# M128_EX.net
KiCad netlist of a schematic drawn in Altium Designer
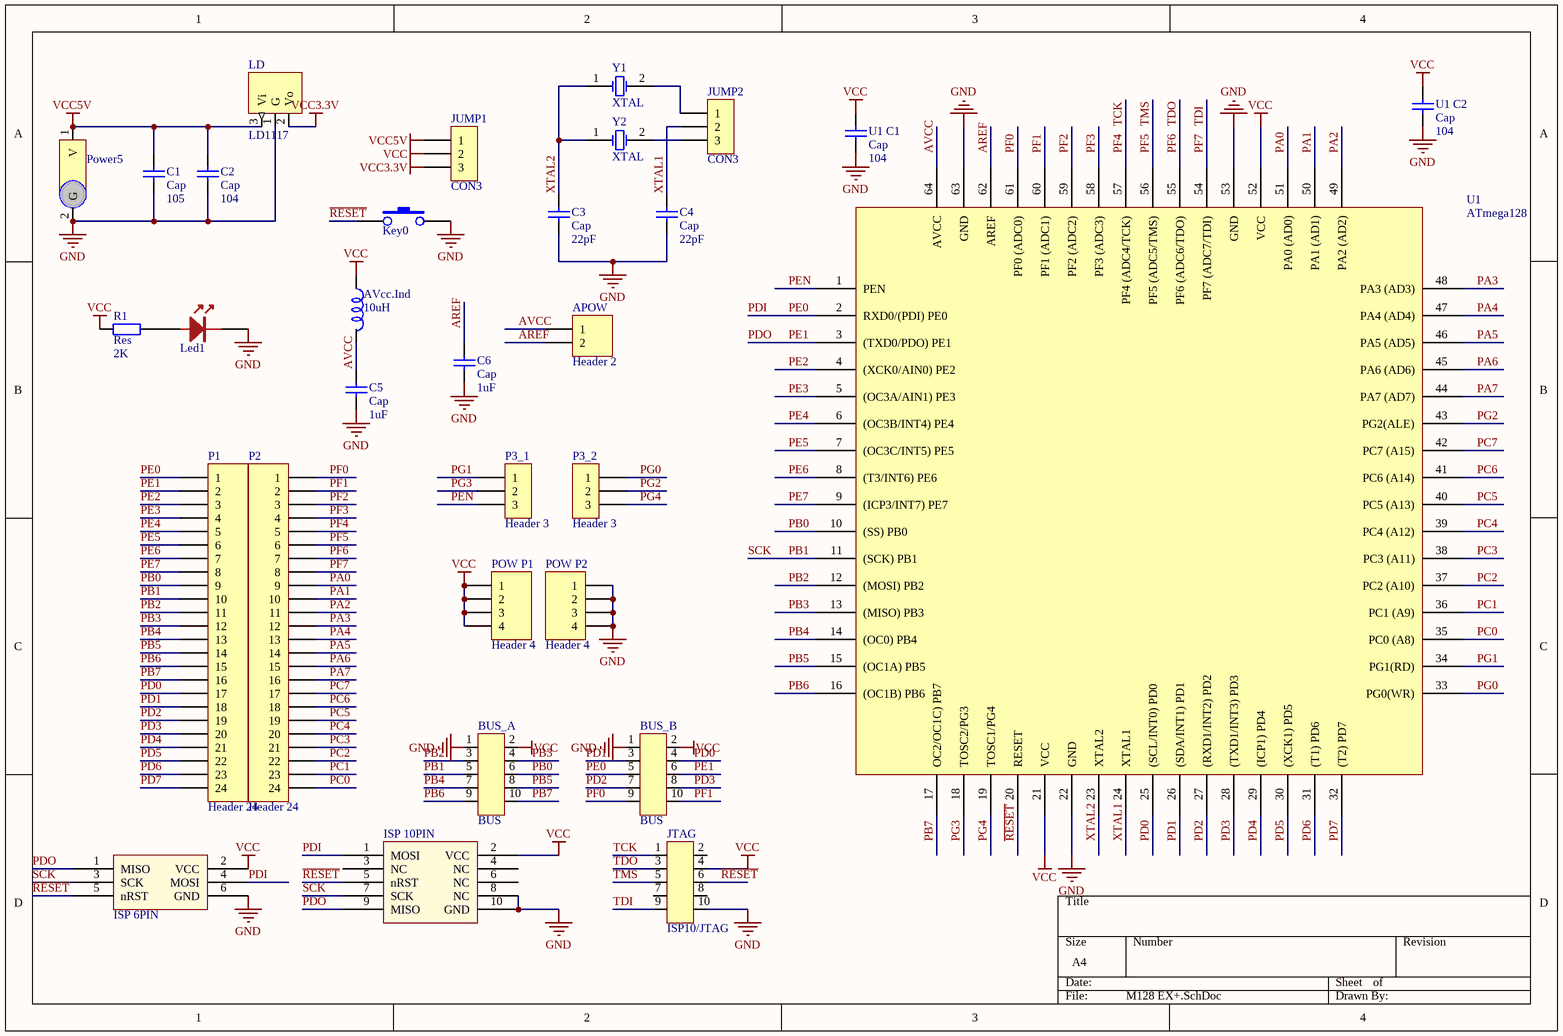
[diagram p0: M128 EX+.SchDoc]

(export (version "E")
  (design (tool "Eeschema 10.0.6"))
  (components
    (comp (ref "APOW")
      (value "Header 2")
      (footprint "SIP2")
      (description "Header, 2-Pin")
      (fields (field (name "PUBLISHER") "Altium Limited"))
      (libsource (lib "zz") (part "Header 2"))
    )
    (comp (ref "AVcc.Ind") (value "10uH") (footprint "RES") (libsource (lib "zz") (part "IND")))
    (comp (ref "BUS_A")
      (value "BUS")
      (footprint "ISP_10")
      (description "ISP_10")
      (libsource (lib "zz") (part "ISP_10"))
    )
    (comp (ref "BUS_B")
      (value "BUS")
      (footprint "ISP_10")
      (description "ISP_10")
      (libsource (lib "zz") (part "ISP_10"))
    )
    (comp (ref "C1")
      (value "Cap")
      (footprint "0805")
      (description "Capacitor")
      (fields (field (name "ALTIUM_VALUE") "105") (field (name "PUBLISHER") "Altium Limited"))
      (libsource (lib "Miscellaneous Devices") (part "Cap"))
    )
    (comp (ref "C2")
      (value "Cap")
      (footprint "0805")
      (description "Capacitor")
      (fields (field (name "ALTIUM_VALUE") "104") (field (name "PUBLISHER") "Altium Limited"))
      (libsource (lib "Miscellaneous Devices") (part "Cap"))
    )
    (comp (ref "C3")
      (value "Cap")
      (footprint "0603")
      (description "Capacitor")
      (fields (field (name "ALTIUM_VALUE") "22pF") (field (name "PUBLISHER") "Altium Limited"))
      (libsource (lib "Miscellaneous Devices") (part "Cap"))
    )
    (comp (ref "C4")
      (value "Cap")
      (footprint "0603")
      (description "Capacitor")
      (fields (field (name "ALTIUM_VALUE") "22pF") (field (name "PUBLISHER") "Altium Limited"))
      (libsource (lib "Miscellaneous Devices") (part "Cap"))
    )
    (comp (ref "C5")
      (value "Cap")
      (footprint "0805")
      (description "Capacitor")
      (fields (field (name "ALTIUM_VALUE") "1uF") (field (name "PUBLISHER") "Altium Limited"))
      (libsource (lib "Miscellaneous Devices") (part "Cap"))
    )
    (comp (ref "C6")
      (value "Cap")
      (footprint "0805")
      (description "Capacitor")
      (fields (field (name "ALTIUM_VALUE") "1uF") (field (name "PUBLISHER") "Altium Limited"))
      (libsource (lib "Miscellaneous Devices") (part "Cap"))
    )
    (comp (ref "ISP 6PIN") (value "ISP 6PIN") (footprint "ISP_6") (libsource (lib "zz") (part "ISP 6PIN")))
    (comp (ref "ISP 10PIN")
      (value "ISP 10PIN")
      (footprint "ISP_10")
      (libsource (lib "zz") (part "ISP 10PIN"))
    )
    (comp (ref "JTAG")
      (value "ISP10/JTAG")
      (footprint "ISP_10")
      (description "ISP_10")
      (libsource (lib "zz") (part "ISP_10"))
    )
    (comp (ref "JUMP1")
      (value "CON3")
      (footprint "SIP3")
      (description "Connector")
      (libsource (lib "zz") (part "CON3"))
    )
    (comp (ref "JUMP2")
      (value "CON3")
      (footprint "SIP3")
      (description "Connector")
      (libsource (lib "zz") (part "CON3"))
    )
    (comp (ref "Key0") (value "PB2") (footprint "KEY") (libsource (lib "zz") (part "KEY")))
    (comp (ref "LD") (value "LD1117") (footprint "LD1117-3.3") (libsource (lib "zz") (part "LD1117")))
    (comp (ref "Led1") (value "Led1") (footprint "0805_LED") (libsource (lib "zz") (part "LED")))
    (comp (ref "P1")
      (value "Header 24")
      (footprint "SIP24")
      (description "Header, 24-Pin")
      (fields (field (name "PUBLISHER") "Altium Limited"))
      (libsource (lib "zz") (part "Header 24"))
    )
    (comp (ref "P2")
      (value "Header 24")
      (footprint "SIP24")
      (description "Header, 24-Pin")
      (fields (field (name "PUBLISHER") "Altium Limited"))
      (libsource (lib "") (part "Header 24_1"))
    )
    (comp (ref "P3_1")
      (value "Header 3")
      (footprint "SIP3")
      (description "Header, 3-Pin")
      (libsource (lib "") (part "Header 3_1"))
    )
    (comp (ref "P3_2")
      (value "Header 3")
      (footprint "SIP3")
      (description "Header, 3-Pin")
      (libsource (lib "zz") (part "Header 3"))
    )
    (comp (ref "POW P1")
      (value "Header 4")
      (footprint "SIP4")
      (description "Header, 4-Pin")
      (fields (field (name "PUBLISHER") "Altium Limited"))
      (libsource (lib "zz") (part "Header 4"))
    )
    (comp (ref "POW P2")
      (value "Header 4")
      (footprint "SIP4")
      (description "Header, 4-Pin")
      (fields (field (name "PUBLISHER") "Altium Limited"))
      (libsource (lib "") (part "Header 4_1"))
    )
    (comp (ref "Power5")
      (value "5V")
      (footprint "PWR_5V")
      (description "Power5")
      (libsource (lib "zz") (part "Power5"))
    )
    (comp (ref "R1")
      (value "Res")
      (footprint "0603")
      (description "Resistor")
      (fields (field (name "ALTIUM_VALUE") "2K") (field (name "PUBLISHER") "Altium Limited"))
      (libsource (lib "Miscellaneous Devices") (part "Res2"))
    )
    (comp (ref "U1") (value "ATmega128") (footprint "TQFP64") (libsource (lib "zz") (part "ATmega128")))
    (comp (ref "U1 C1")
      (value "Cap")
      (footprint "0805")
      (description "Capacitor")
      (fields (field (name "ALTIUM_VALUE") "104") (field (name "PUBLISHER") "Altium Limited"))
      (libsource (lib "Miscellaneous Devices") (part "Cap"))
    )
    (comp (ref "U1 C2")
      (value "Cap")
      (footprint "0805")
      (description "Capacitor")
      (fields (field (name "ALTIUM_VALUE") "104") (field (name "PUBLISHER") "Altium Limited"))
      (libsource (lib "Miscellaneous Devices") (part "Cap"))
    )
    (comp (ref "Y1")
      (value "XTAL")
      (footprint "CRYSTAL")
      (description "Crystal Oscillator")
      (fields (field (name "PUBLISHER") "Altium Limited"))
      (libsource (lib "zz") (part "XTAL"))
    )
    (comp (ref "Y2")
      (value "XTAL")
      (footprint "CRYSTAL2")
      (description "Crystal Oscillator")
      (fields (field (name "PUBLISHER") "Altium Limited"))
      (libsource (lib "zz") (part "XTAL"))
    )
  )
  (nets
    (net (code "1") (name "/AREF") (class "Default")
      (node (ref "APOW") (pin "2") (pinfunction "2_2") (pintype "passive"))
      (node (ref "C6") (pin "2") (pinfunction "2_2") (pintype "passive"))
      (node (ref "U1") (pin "62") (pinfunction "AREF_62") (pintype "passive"))
    )
    (net (code "2") (name "/AVCC") (class "Default")
      (node (ref "APOW") (pin "1") (pinfunction "1_1") (pintype "passive"))
      (node (ref "AVcc.Ind") (pin "2") (pinfunction "1_2") (pintype "passive"))
      (node (ref "C5") (pin "2") (pinfunction "2_2") (pintype "passive"))
      (node (ref "U1") (pin "64") (pinfunction "AVCC_64") (pintype "passive"))
    )
    (net (code "3") (name "/PA0") (class "Default")
      (node (ref "P2") (pin "9") (pinfunction "9_9") (pintype "passive"))
      (node (ref "U1") (pin "51") (pinfunction "PA0_(AD0)_51") (pintype "passive"))
    )
    (net (code "4") (name "/PA1") (class "Default")
      (node (ref "P2") (pin "10") (pinfunction "10_10") (pintype "passive"))
      (node (ref "U1") (pin "50") (pinfunction "PA1_(AD1)_50") (pintype "passive"))
    )
    (net (code "5") (name "/PA2") (class "Default")
      (node (ref "P2") (pin "11") (pinfunction "11_11") (pintype "passive"))
      (node (ref "U1") (pin "49") (pinfunction "PA2_(AD2)_49") (pintype "passive"))
    )
    (net (code "6") (name "/PA3") (class "Default")
      (node (ref "P2") (pin "12") (pinfunction "12_12") (pintype "passive"))
      (node (ref "U1") (pin "48") (pinfunction "PA3_(AD3)_48") (pintype "passive"))
    )
    (net (code "7") (name "/PA4") (class "Default")
      (node (ref "P2") (pin "13") (pinfunction "13_13") (pintype "passive"))
      (node (ref "U1") (pin "47") (pinfunction "PA4_(AD4)_47") (pintype "passive"))
    )
    (net (code "8") (name "/PA5") (class "Default")
      (node (ref "P2") (pin "14") (pinfunction "14_14") (pintype "passive"))
      (node (ref "U1") (pin "46") (pinfunction "PA5_(AD5)_46") (pintype "passive"))
    )
    (net (code "9") (name "/PA6") (class "Default")
      (node (ref "P2") (pin "15") (pinfunction "15_15") (pintype "passive"))
      (node (ref "U1") (pin "45") (pinfunction "PA6_(AD6)_45") (pintype "passive"))
    )
    (net (code "10") (name "/PA7") (class "Default")
      (node (ref "P2") (pin "16") (pinfunction "16_16") (pintype "passive"))
      (node (ref "U1") (pin "44") (pinfunction "PA7_(AD7)_44") (pintype "passive"))
    )
    (net (code "11") (name "/PB0") (class "Default")
      (node (ref "BUS_A") (pin "6") (pintype "passive"))
      (node (ref "P1") (pin "9") (pinfunction "9_9") (pintype "passive"))
      (node (ref "U1") (pin "10") (pinfunction "(SS)_PB0_10") (pintype "passive"))
    )
    (net (code "12") (name "/PB1") (class "Default")
      (node (ref "BUS_A") (pin "5") (pintype "passive"))
      (node (ref "ISP 10PIN") (pin "7") (pinfunction "SCK_7") (pintype "passive"))
      (node (ref "ISP 6PIN") (pin "3") (pinfunction "SCK_3") (pintype "passive"))
      (node (ref "P1") (pin "10") (pinfunction "10_10") (pintype "passive"))
      (node (ref "U1") (pin "11") (pinfunction "(SCK)_PB1_11") (pintype "passive"))
    )
    (net (code "13") (name "/PB2") (class "Default")
      (node (ref "BUS_A") (pin "3") (pintype "passive"))
      (node (ref "P1") (pin "11") (pinfunction "11_11") (pintype "passive"))
      (node (ref "U1") (pin "12") (pinfunction "(MOSI)_PB2_12") (pintype "passive"))
    )
    (net (code "14") (name "/PB3") (class "Default")
      (node (ref "BUS_A") (pin "4") (pintype "passive"))
      (node (ref "P1") (pin "12") (pinfunction "12_12") (pintype "passive"))
      (node (ref "U1") (pin "13") (pinfunction "(MISO)_PB3_13") (pintype "passive"))
    )
    (net (code "15") (name "/PB4") (class "Default")
      (node (ref "BUS_A") (pin "7") (pintype "passive"))
      (node (ref "P1") (pin "13") (pinfunction "13_13") (pintype "passive"))
      (node (ref "U1") (pin "14") (pinfunction "(OC0)_PB4_14") (pintype "passive"))
    )
    (net (code "16") (name "/PB5") (class "Default")
      (node (ref "BUS_A") (pin "8") (pintype "passive"))
      (node (ref "P1") (pin "14") (pinfunction "14_14") (pintype "passive"))
      (node (ref "U1") (pin "15") (pinfunction "(OC1A)_PB5_15") (pintype "passive"))
    )
    (net (code "17") (name "/PB6") (class "Default")
      (node (ref "BUS_A") (pin "9") (pintype "passive"))
      (node (ref "P1") (pin "15") (pinfunction "15_15") (pintype "passive"))
      (node (ref "U1") (pin "16") (pinfunction "(OC1B)_PB6_16") (pintype "passive"))
    )
    (net (code "18") (name "/PB7") (class "Default")
      (node (ref "BUS_A") (pin "10") (pintype "passive"))
      (node (ref "P1") (pin "16") (pinfunction "16_16") (pintype "passive"))
      (node (ref "U1") (pin "17") (pinfunction "OC2/OC1C)_PB7_17") (pintype "passive"))
    )
    (net (code "19") (name "/PC0") (class "Default")
      (node (ref "P2") (pin "24") (pinfunction "24_24") (pintype "passive"))
      (node (ref "U1") (pin "35") (pinfunction "PC0_(A8)_35") (pintype "passive"))
    )
    (net (code "20") (name "/PC1") (class "Default")
      (node (ref "P2") (pin "23") (pinfunction "23_23") (pintype "passive"))
      (node (ref "U1") (pin "36") (pinfunction "PC1_(A9)_36") (pintype "passive"))
    )
    (net (code "21") (name "/PC2") (class "Default")
      (node (ref "P2") (pin "22") (pinfunction "22_22") (pintype "passive"))
      (node (ref "U1") (pin "37") (pinfunction "PC2_(A10)_37") (pintype "passive"))
    )
    (net (code "22") (name "/PC3") (class "Default")
      (node (ref "P2") (pin "21") (pinfunction "21_21") (pintype "passive"))
      (node (ref "U1") (pin "38") (pinfunction "PC3_(A11)_38") (pintype "passive"))
    )
    (net (code "23") (name "/PC4") (class "Default")
      (node (ref "P2") (pin "20") (pinfunction "20_20") (pintype "passive"))
      (node (ref "U1") (pin "39") (pinfunction "PC4_(A12)_39") (pintype "passive"))
    )
    (net (code "24") (name "/PC5") (class "Default")
      (node (ref "P2") (pin "19") (pinfunction "19_19") (pintype "passive"))
      (node (ref "U1") (pin "40") (pinfunction "PC5_(A13)_40") (pintype "passive"))
    )
    (net (code "25") (name "/PC6") (class "Default")
      (node (ref "P2") (pin "18") (pinfunction "18_18") (pintype "passive"))
      (node (ref "U1") (pin "41") (pinfunction "PC6_(A14)_41") (pintype "passive"))
    )
    (net (code "26") (name "/PC7") (class "Default")
      (node (ref "P2") (pin "17") (pinfunction "17_17") (pintype "passive"))
      (node (ref "U1") (pin "42") (pinfunction "PC7_(A15)_42") (pintype "passive"))
    )
    (net (code "27") (name "/PD0") (class "Default")
      (node (ref "BUS_B") (pin "4") (pintype "passive"))
      (node (ref "P1") (pin "17") (pinfunction "17_17") (pintype "passive"))
      (node (ref "U1") (pin "25") (pinfunction "(SCL/INT0)_PD0_25") (pintype "passive"))
    )
    (net (code "28") (name "/PD1") (class "Default")
      (node (ref "BUS_B") (pin "3") (pintype "passive"))
      (node (ref "P1") (pin "18") (pinfunction "18_18") (pintype "passive"))
      (node (ref "U1") (pin "26") (pinfunction "(SDA/INT1)_PD1_26") (pintype "passive"))
    )
    (net (code "29") (name "/PD2") (class "Default")
      (node (ref "BUS_B") (pin "7") (pintype "passive"))
      (node (ref "P1") (pin "19") (pinfunction "19_19") (pintype "passive"))
      (node (ref "U1") (pin "27") (pinfunction "(RXD1/INT2)_PD2_27") (pintype "passive"))
    )
    (net (code "30") (name "/PD3") (class "Default")
      (node (ref "BUS_B") (pin "8") (pintype "passive"))
      (node (ref "P1") (pin "20") (pinfunction "20_20") (pintype "passive"))
      (node (ref "U1") (pin "28") (pinfunction "(TXD1/INT3)_PD3_28") (pintype "passive"))
    )
    (net (code "31") (name "/PD4") (class "Default")
      (node (ref "P1") (pin "21") (pinfunction "21_21") (pintype "passive"))
      (node (ref "U1") (pin "29") (pinfunction "(ICP1)_PD4_29") (pintype "passive"))
    )
    (net (code "32") (name "/PD5") (class "Default")
      (node (ref "P1") (pin "22") (pinfunction "22_22") (pintype "passive"))
      (node (ref "U1") (pin "30") (pinfunction "(XCK1)_PD5_30") (pintype "passive"))
    )
    (net (code "33") (name "/PD6") (class "Default")
      (node (ref "P1") (pin "23") (pinfunction "23_23") (pintype "passive"))
      (node (ref "U1") (pin "31") (pinfunction "(T1)_PD6_31") (pintype "passive"))
    )
    (net (code "34") (name "/PD7") (class "Default")
      (node (ref "P1") (pin "24") (pinfunction "24_24") (pintype "passive"))
      (node (ref "U1") (pin "32") (pinfunction "(T2)_PD7_32") (pintype "passive"))
    )
    (net (code "35") (name "/PDI") (class "Default")
      (node (ref "BUS_B") (pin "5") (pintype "passive"))
      (node (ref "ISP 10PIN") (pin "1") (pinfunction "MOSI_1") (pintype "passive"))
      (node (ref "ISP 6PIN") (pin "4") (pinfunction "MOSI_4") (pintype "passive"))
      (node (ref "P1") (pin "1") (pinfunction "1_1") (pintype "passive"))
      (node (ref "U1") (pin "2") (pinfunction "RXD0/(PDI)_PE0_2") (pintype "passive"))
    )
    (net (code "36") (name "/PDO") (class "Default")
      (node (ref "BUS_B") (pin "6") (pintype "passive"))
      (node (ref "ISP 10PIN") (pin "9") (pinfunction "MISO_9") (pintype "passive"))
      (node (ref "ISP 6PIN") (pin "1") (pinfunction "MISO_1") (pintype "passive"))
      (node (ref "P1") (pin "2") (pinfunction "2_2") (pintype "passive"))
      (node (ref "U1") (pin "3") (pinfunction "(TXD0/PDO)_PE1_3") (pintype "passive"))
    )
    (net (code "37") (name "/PE2") (class "Default")
      (node (ref "P1") (pin "3") (pinfunction "3_3") (pintype "passive"))
      (node (ref "U1") (pin "4") (pinfunction "(XCK0/AIN0)_PE2_4") (pintype "passive"))
    )
    (net (code "38") (name "/PE3") (class "Default")
      (node (ref "P1") (pin "4") (pinfunction "4_4") (pintype "passive"))
      (node (ref "U1") (pin "5") (pinfunction "(OC3A/AIN1)_PE3_5") (pintype "passive"))
    )
    (net (code "39") (name "/PE4") (class "Default")
      (node (ref "P1") (pin "5") (pinfunction "5_5") (pintype "passive"))
      (node (ref "U1") (pin "6") (pinfunction "(OC3B/INT4)_PE4_6") (pintype "passive"))
    )
    (net (code "40") (name "/PE5") (class "Default")
      (node (ref "P1") (pin "6") (pinfunction "6_6") (pintype "passive"))
      (node (ref "U1") (pin "7") (pinfunction "(OC3C/INT5)_PE5_7") (pintype "passive"))
    )
    (net (code "41") (name "/PE6") (class "Default")
      (node (ref "P1") (pin "7") (pinfunction "7_7") (pintype "passive"))
      (node (ref "U1") (pin "8") (pinfunction "(T3/INT6)_PE6_8") (pintype "passive"))
    )
    (net (code "42") (name "/PE7") (class "Default")
      (node (ref "P1") (pin "8") (pinfunction "8_8") (pintype "passive"))
      (node (ref "U1") (pin "9") (pinfunction "(ICP3/INT7)_PE7_9") (pintype "passive"))
    )
    (net (code "43") (name "/PEN") (class "Default")
      (node (ref "P3_1") (pin "3") (pinfunction "3_3") (pintype "passive"))
      (node (ref "U1") (pin "1") (pinfunction "PEN_1") (pintype "passive"))
    )
    (net (code "44") (name "/PF0") (class "Default")
      (node (ref "BUS_B") (pin "9") (pintype "passive"))
      (node (ref "P2") (pin "1") (pinfunction "1_1") (pintype "passive"))
      (node (ref "U1") (pin "61") (pinfunction "PF0_(ADC0)_61") (pintype "passive"))
    )
    (net (code "45") (name "/PF1") (class "Default")
      (node (ref "BUS_B") (pin "10") (pintype "passive"))
      (node (ref "P2") (pin "2") (pinfunction "2_2") (pintype "passive"))
      (node (ref "U1") (pin "60") (pinfunction "PF1_(ADC1)_60") (pintype "passive"))
    )
    (net (code "46") (name "/PF2") (class "Default")
      (node (ref "P2") (pin "3") (pinfunction "3_3") (pintype "passive"))
      (node (ref "U1") (pin "59") (pinfunction "PF2_(ADC2)_59") (pintype "passive"))
    )
    (net (code "47") (name "/PF3") (class "Default")
      (node (ref "P2") (pin "4") (pinfunction "4_4") (pintype "passive"))
      (node (ref "U1") (pin "58") (pinfunction "PF3_(ADC3)_58") (pintype "passive"))
    )
    (net (code "48") (name "/PF4") (class "Default")
      (node (ref "JTAG") (pin "1") (pintype "passive"))
      (node (ref "P2") (pin "5") (pinfunction "5_5") (pintype "passive"))
      (node (ref "U1") (pin "57") (pinfunction "PF4_(ADC4/TCK)_57") (pintype "passive"))
    )
    (net (code "49") (name "/PF5") (class "Default")
      (node (ref "JTAG") (pin "5") (pintype "passive"))
      (node (ref "P2") (pin "6") (pinfunction "6_6") (pintype "passive"))
      (node (ref "U1") (pin "56") (pinfunction "PF5_(ADC5/TMS)_56") (pintype "passive"))
    )
    (net (code "50") (name "/PF6") (class "Default")
      (node (ref "JTAG") (pin "3") (pintype "passive"))
      (node (ref "P2") (pin "7") (pinfunction "7_7") (pintype "passive"))
      (node (ref "U1") (pin "55") (pinfunction "PF6_(ADC6/TDO)_55") (pintype "passive"))
    )
    (net (code "51") (name "/PF7") (class "Default")
      (node (ref "JTAG") (pin "9") (pintype "passive"))
      (node (ref "P2") (pin "8") (pinfunction "8_8") (pintype "passive"))
      (node (ref "U1") (pin "54") (pinfunction "PF7_(ADC7/TDI)_54") (pintype "passive"))
    )
    (net (code "52") (name "/PG0") (class "Default")
      (node (ref "P3_2") (pin "1") (pinfunction "1_1") (pintype "passive"))
      (node (ref "U1") (pin "33") (pinfunction "PG0(WR)_33") (pintype "passive"))
    )
    (net (code "53") (name "/PG1") (class "Default")
      (node (ref "P3_1") (pin "1") (pinfunction "1_1") (pintype "passive"))
      (node (ref "U1") (pin "34") (pinfunction "PG1(RD)_34") (pintype "passive"))
    )
    (net (code "54") (name "/PG2") (class "Default")
      (node (ref "P3_2") (pin "2") (pinfunction "2_2") (pintype "passive"))
      (node (ref "U1") (pin "43") (pinfunction "PG2(ALE)_43") (pintype "passive"))
    )
    (net (code "55") (name "/PG3") (class "Default")
      (node (ref "P3_1") (pin "2") (pinfunction "2_2") (pintype "passive"))
      (node (ref "U1") (pin "18") (pinfunction "TOSC2/PG3_18") (pintype "passive"))
    )
    (net (code "56") (name "/PG4") (class "Default")
      (node (ref "P3_2") (pin "3") (pinfunction "3_3") (pintype "passive"))
      (node (ref "U1") (pin "19") (pinfunction "TOSC1/PG4_19") (pintype "passive"))
    )
    (net (code "57") (name "/XTAL1") (class "Default")
      (node (ref "C4") (pin "2") (pinfunction "2_2") (pintype "passive"))
      (node (ref "JUMP2") (pin "2") (pinfunction "2_2") (pintype "passive"))
      (node (ref "U1") (pin "24") (pinfunction "XTAL1_24") (pintype "passive"))
    )
    (net (code "58") (name "/XTAL2") (class "Default")
      (node (ref "C3") (pin "2") (pinfunction "2_2") (pintype "passive"))
      (node (ref "U1") (pin "23") (pinfunction "XTAL2_23") (pintype "passive"))
      (node (ref "Y1") (pin "1") (pinfunction "OSC1_1") (pintype "passive"))
      (node (ref "Y2") (pin "1") (pinfunction "OSC1_1") (pintype "passive"))
    )
    (net (code "59") (name "/~{RESET}") (class "Default")
      (node (ref "ISP 10PIN") (pin "5") (pinfunction "nRST_5") (pintype "passive"))
      (node (ref "ISP 6PIN") (pin "5") (pinfunction "nRST_5") (pintype "passive"))
      (node (ref "JTAG") (pin "6") (pintype "passive"))
      (node (ref "Key0") (pin "1") (pinfunction "1_1") (pintype "passive"))
      (node (ref "U1") (pin "20") (pinfunction "RESET_20") (pintype "passive"))
    )
    (net (code "60") (name "GND") (class "Default")
      (node (ref "BUS_A") (pin "1") (pintype "passive"))
      (node (ref "BUS_B") (pin "1") (pintype "passive"))
      (node (ref "C1") (pin "1") (pinfunction "1_1") (pintype "passive"))
      (node (ref "C2") (pin "1") (pinfunction "1_1") (pintype "passive"))
      (node (ref "C3") (pin "1") (pinfunction "1_1") (pintype "passive"))
      (node (ref "C4") (pin "1") (pinfunction "1_1") (pintype "passive"))
      (node (ref "C5") (pin "1") (pinfunction "1_1") (pintype "passive"))
      (node (ref "C6") (pin "1") (pinfunction "1_1") (pintype "passive"))
      (node (ref "ISP 10PIN") (pin "10") (pinfunction "GND_10") (pintype "passive"))
      (node (ref "ISP 10PIN") (pin "8") (pinfunction "NC_8") (pintype "passive"))
      (node (ref "ISP 6PIN") (pin "6") (pinfunction "GND_6") (pintype "passive"))
      (node (ref "JTAG") (pin "10") (pintype "passive"))
      (node (ref "Key0") (pin "2") (pinfunction "2_2") (pintype "passive"))
      (node (ref "LD") (pin "1") (pinfunction "G_1") (pintype "passive"))
      (node (ref "Led1") (pin "2") (pinfunction "2_2") (pintype "passive"))
      (node (ref "POW P2") (pin "1") (pinfunction "1_1") (pintype "passive"))
      (node (ref "POW P2") (pin "2") (pinfunction "2_2") (pintype "passive"))
      (node (ref "POW P2") (pin "3") (pinfunction "3_3") (pintype "passive"))
      (node (ref "POW P2") (pin "4") (pinfunction "4_4") (pintype "passive"))
      (node (ref "Power5") (pin "2") (pinfunction "G_2") (pintype "passive"))
      (node (ref "U1") (pin "22") (pinfunction "GND_22") (pintype "passive"))
      (node (ref "U1") (pin "53") (pinfunction "GND_53") (pintype "passive"))
      (node (ref "U1") (pin "63") (pinfunction "GND_63") (pintype "passive"))
      (node (ref "U1 C1") (pin "1") (pinfunction "1_1") (pintype "passive"))
      (node (ref "U1 C2") (pin "1") (pinfunction "1_1") (pintype "passive"))
    )
    (net (code "61") (name "Net-(Led1-Pad1)") (class "Default")
      (node (ref "Led1") (pin "1") (pinfunction "1_1") (pintype "passive"))
      (node (ref "R1") (pin "1") (pinfunction "1_1") (pintype "passive"))
    )
    (net (code "62") (name "Net-(Y1-OSC2)") (class "Default")
      (node (ref "JUMP2") (pin "1") (pinfunction "1_1") (pintype "passive"))
      (node (ref "Y1") (pin "2") (pinfunction "OSC2_2") (pintype "passive"))
    )
    (net (code "63") (name "Net-(Y2-OSC2)") (class "Default")
      (node (ref "JUMP2") (pin "3") (pinfunction "3_3") (pintype "passive"))
      (node (ref "Y2") (pin "2") (pinfunction "OSC2_2") (pintype "passive"))
    )
    (net (code "64") (name "VCC") (class "Default")
      (node (ref "AVcc.Ind") (pin "1") (pinfunction "0_1") (pintype "passive"))
      (node (ref "BUS_A") (pin "2") (pintype "passive"))
      (node (ref "BUS_B") (pin "2") (pintype "passive"))
      (node (ref "ISP 10PIN") (pin "2") (pinfunction "VCC_2") (pintype "passive"))
      (node (ref "ISP 6PIN") (pin "2") (pinfunction "VCC_2") (pintype "passive"))
      (node (ref "JTAG") (pin "4") (pintype "passive"))
      (node (ref "JUMP1") (pin "2") (pinfunction "2_2") (pintype "passive"))
      (node (ref "POW P1") (pin "1") (pinfunction "1_1") (pintype "passive"))
      (node (ref "POW P1") (pin "2") (pinfunction "2_2") (pintype "passive"))
      (node (ref "POW P1") (pin "3") (pinfunction "3_3") (pintype "passive"))
      (node (ref "POW P1") (pin "4") (pinfunction "4_4") (pintype "passive"))
      (node (ref "R1") (pin "2") (pinfunction "2_2") (pintype "passive"))
      (node (ref "U1") (pin "21") (pinfunction "VCC_21") (pintype "passive"))
      (node (ref "U1") (pin "52") (pinfunction "VCC_52") (pintype "passive"))
      (node (ref "U1 C1") (pin "2") (pinfunction "2_2") (pintype "passive"))
      (node (ref "U1 C2") (pin "2") (pinfunction "2_2") (pintype "passive"))
    )
    (net (code "65") (name "VCC3.3V") (class "Default")
      (node (ref "JUMP1") (pin "3") (pinfunction "3_3") (pintype "passive"))
      (node (ref "LD") (pin "2") (pinfunction "Vo_2") (pintype "passive"))
    )
    (net (code "66") (name "VCC5V") (class "Default")
      (node (ref "C1") (pin "2") (pinfunction "2_2") (pintype "passive"))
      (node (ref "C2") (pin "2") (pinfunction "2_2") (pintype "passive"))
      (node (ref "JUMP1") (pin "1") (pinfunction "1_1") (pintype "passive"))
      (node (ref "LD") (pin "3") (pinfunction "Vi_3") (pintype "output"))
      (node (ref "Power5") (pin "1") (pinfunction "V_1") (pintype "passive"))
    )
    (net (code "67") (name "unconnected-(ISP 10PIN-NC-Pad3)") (class "Default")
      (node (ref "ISP 10PIN") (pin "3") (pinfunction "NC_3") (pintype "passive"))
    )
    (net (code "68") (name "unconnected-(ISP 10PIN-NC-Pad4)") (class "Default")
      (node (ref "ISP 10PIN") (pin "4") (pinfunction "NC_4") (pintype "passive"))
    )
    (net (code "69") (name "unconnected-(ISP 10PIN-NC-Pad6)") (class "Default")
      (node (ref "ISP 10PIN") (pin "6") (pinfunction "NC_6") (pintype "passive"))
    )
    (net (code "70") (name "unconnected-(JTAG-Pad2)") (class "Default")
      (node (ref "JTAG") (pin "2") (pintype "passive"))
    )
    (net (code "71") (name "unconnected-(JTAG-Pad7)") (class "Default")
      (node (ref "JTAG") (pin "7") (pintype "passive"))
    )
    (net (code "72") (name "unconnected-(JTAG-Pad8)") (class "Default")
      (node (ref "JTAG") (pin "8") (pintype "passive"))
    )
  )
)
